# 07_RFID_LCD.net
KiCad netlist of a schematic drawn in Altium Designer
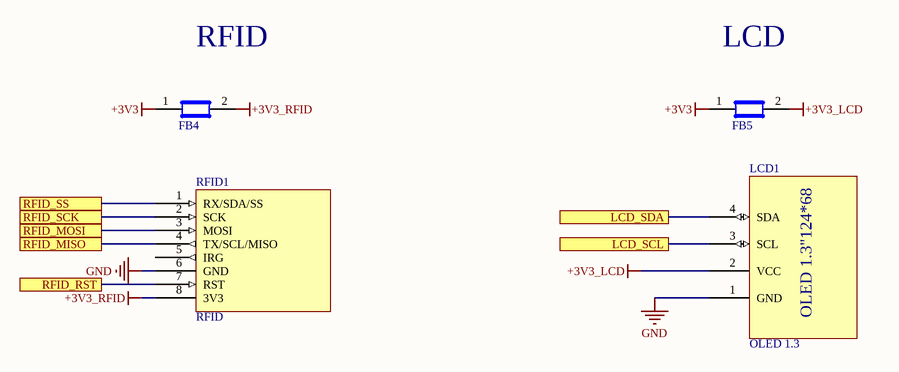
[diagram p0: [07] RFID_LCD.SchDoc]

(export (version "E")
  (design (tool "Eeschema 10.0.6"))
  (components
    (comp (ref "FB4")
      (value "BLM21PG600SN1D")
      (footprint "R0805")
      (description "Ferrite Bead")
      (libsource (lib "GPS_Traking_V1_1") (part "Ferrite Bead"))
    )
    (comp (ref "FB5")
      (value "BLM21PG600SN1D")
      (footprint "R0805")
      (description "Ferrite Bead")
      (libsource (lib "GPS_Traking_V1_1") (part "Ferrite Bead"))
    )
    (comp (ref "LCD1")
      (value "OLED 1.3")
      (footprint "OLED 1.3")
      (libsource (lib "My Library") (part "OLED 1.3"))
    )
    (comp (ref "RFID1")
      (value "RFID")
      (footprint "RFID RC522")
      (libsource (lib "My Library") (part "RFID RC522"))
    )
  )
  (nets
    (net (code "1") (name "+3V3") (class "Default")
      (node (ref "FB4") (pin "1") (pinfunction "1_1") (pintype "passive"))
      (node (ref "FB5") (pin "1") (pinfunction "1_1") (pintype "passive"))
    )
    (net (code "2") (name "+3V3_LCD") (class "Default")
      (node (ref "FB5") (pin "2") (pinfunction "2_2") (pintype "passive"))
      (node (ref "LCD1") (pin "2") (pinfunction "VCC_2") (pintype "power_in"))
    )
    (net (code "3") (name "+3V3_RFID") (class "Default")
      (node (ref "FB4") (pin "2") (pinfunction "2_2") (pintype "passive"))
      (node (ref "RFID1") (pin "8") (pinfunction "3V3_8") (pintype "power_in"))
    )
    (net (code "4") (name "/LCD_SCL") (class "Default")
      (node (ref "LCD1") (pin "3") (pinfunction "SCL_3") (pintype "bidirectional"))
    )
    (net (code "5") (name "/LCD_SDA") (class "Default")
      (node (ref "LCD1") (pin "4") (pinfunction "SDA_4") (pintype "bidirectional"))
    )
    (net (code "6") (name "/RFID_MISO") (class "Default")
      (node (ref "RFID1") (pin "4") (pinfunction "TX/SCL/MISO_4") (pintype "output"))
    )
    (net (code "7") (name "/RFID_MOSI") (class "Default")
      (node (ref "RFID1") (pin "3") (pinfunction "MOSI_3") (pintype "input"))
    )
    (net (code "8") (name "/RFID_RST") (class "Default")
      (node (ref "RFID1") (pin "7") (pinfunction "RST_7") (pintype "input"))
    )
    (net (code "9") (name "/RFID_SCK") (class "Default")
      (node (ref "RFID1") (pin "2") (pinfunction "SCK_2") (pintype "input"))
    )
    (net (code "10") (name "/RFID_SS") (class "Default")
      (node (ref "RFID1") (pin "1") (pinfunction "RX/SDA/SS_1") (pintype "input"))
    )
    (net (code "11") (name "GND") (class "Default")
      (node (ref "LCD1") (pin "1") (pinfunction "GND_1") (pintype "power_in"))
      (node (ref "RFID1") (pin "6") (pinfunction "GND_6") (pintype "power_in"))
    )
    (net (code "12") (name "unconnected-(RFID1-IRG-Pad5)") (class "Default")
      (node (ref "RFID1") (pin "5") (pinfunction "IRG_5") (pintype "output"))
    )
  )
)
